# LeftHandPath.net
KiCad netlist of a schematic drawn in EAGLE
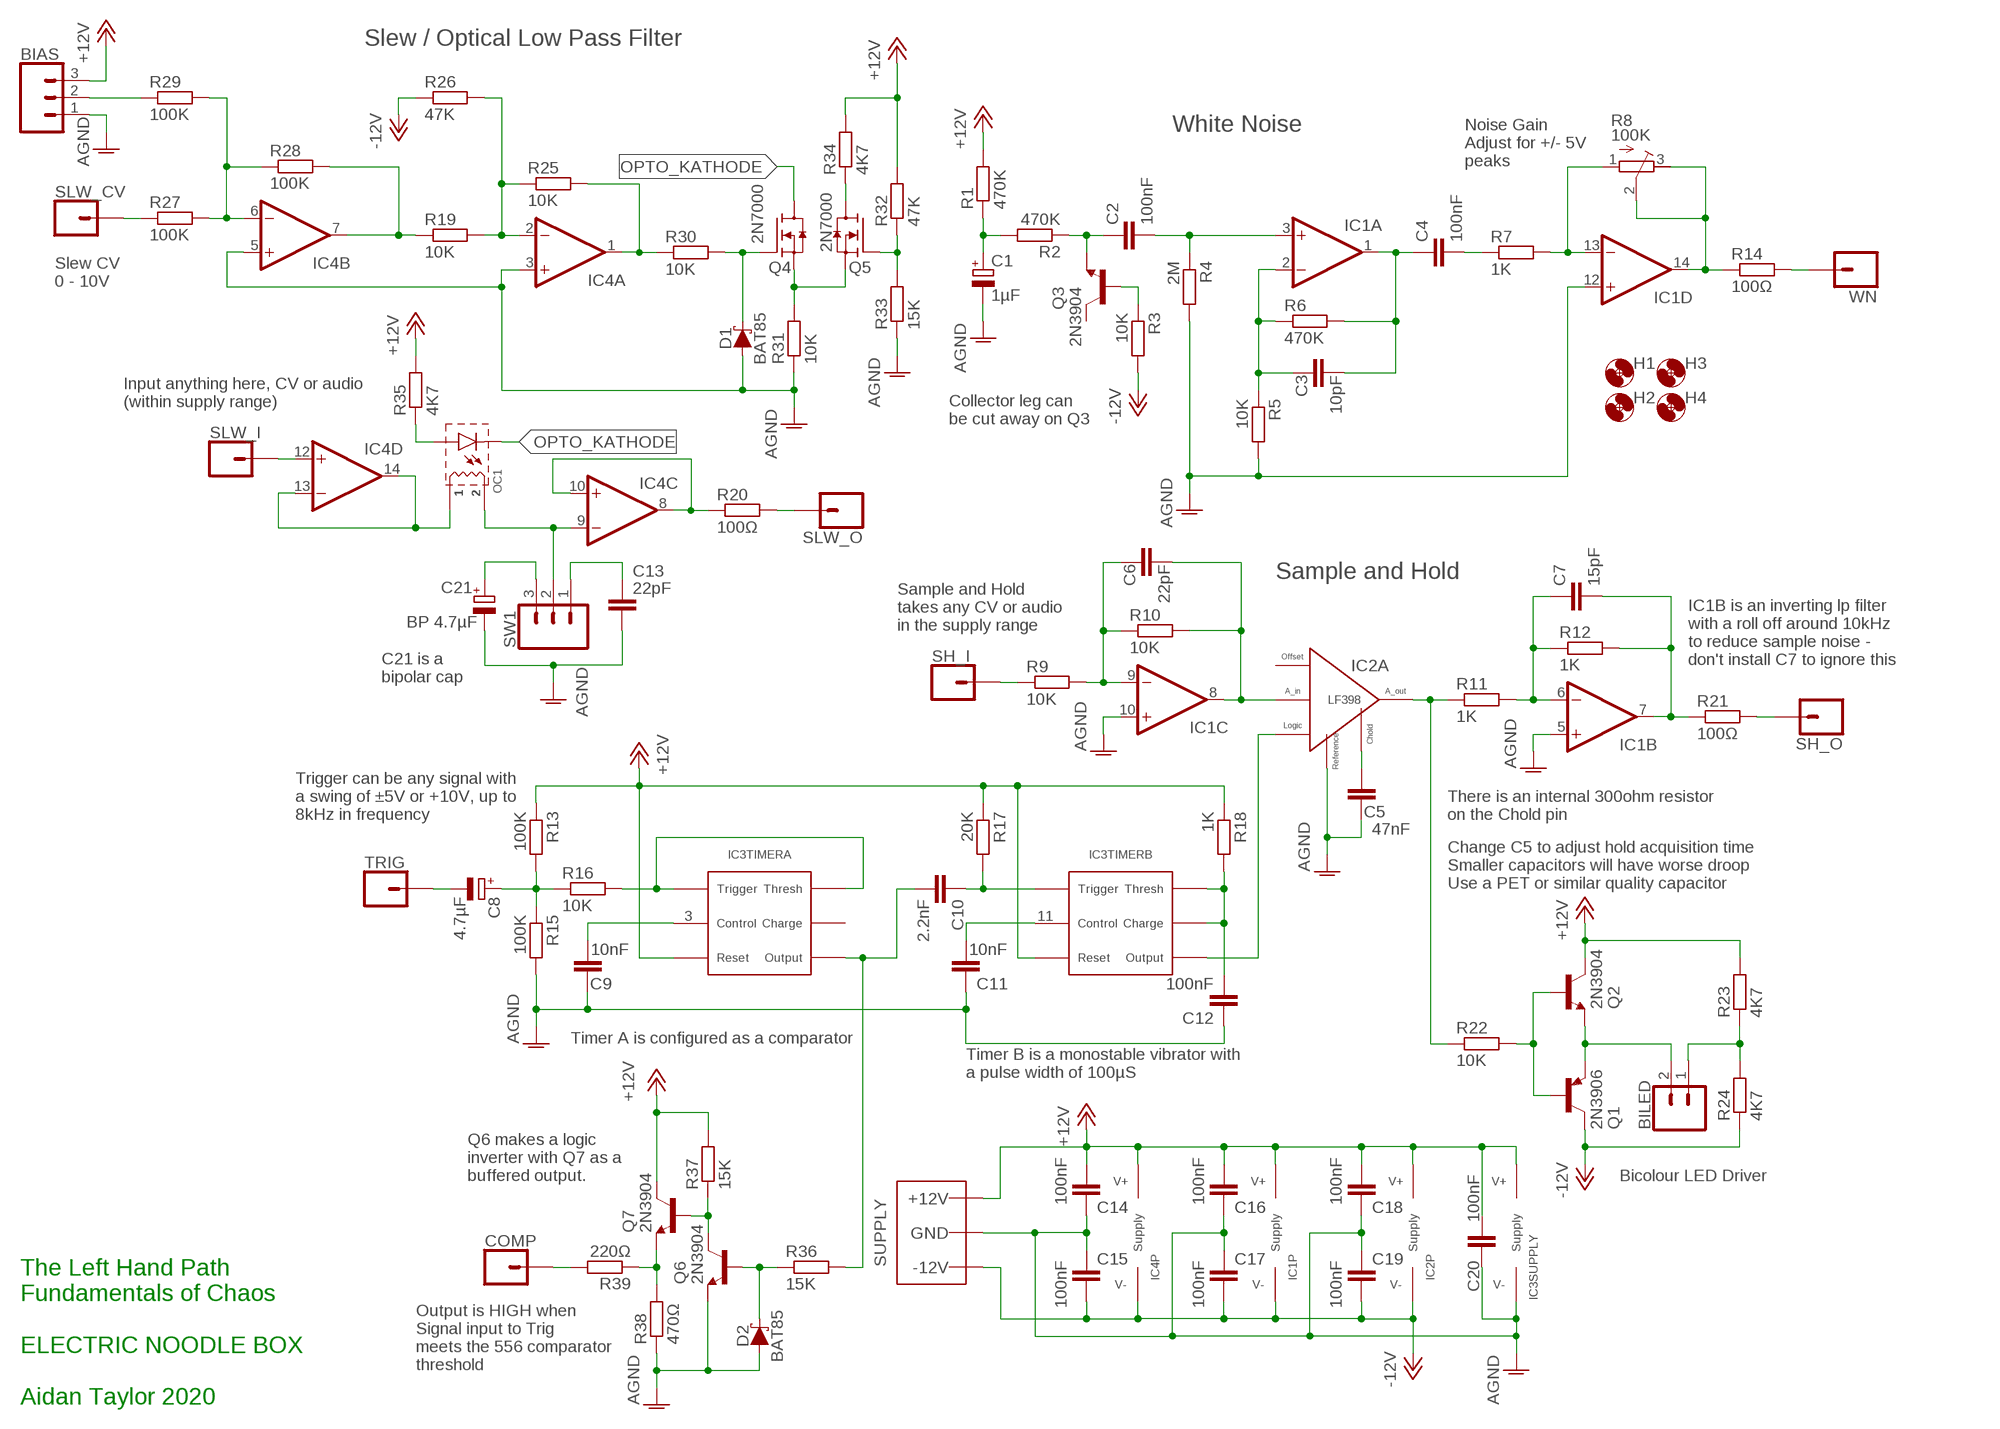
[diagram p0: schematic, sheet 1]

(export (version "E")
  (design (tool "Eeschema 10.0.6"))
  (components
    (comp (ref "BIAS")
      (value "3XWIREPAD")
      (footprint "eagle-import:1X03")
      (libsource (lib "eagle-import") (part "3XWIREPAD"))
    )
    (comp (ref "BILED")
      (value "2XWIREPAD")
      (footprint "eagle-import:1X02")
      (libsource (lib "eagle-import") (part "2XWIREPAD"))
    )
    (comp (ref "C1")
      (value "1µF")
      (footprint "eagle-import:E2-5")
      (libsource (lib "eagle-import") (part "CPOL-EUE2-5"))
    )
    (comp (ref "C2")
      (value "100nF")
      (footprint "eagle-import:C050-025X075")
      (libsource (lib "eagle-import") (part "C-EU050-025X075"))
    )
    (comp (ref "C3")
      (value "10pF")
      (footprint "eagle-import:C050-025X075")
      (libsource (lib "eagle-import") (part "C-EU050-025X075"))
    )
    (comp (ref "C4")
      (value "100nF")
      (footprint "eagle-import:C050-025X075")
      (libsource (lib "eagle-import") (part "C-EU050-025X075"))
    )
    (comp (ref "C5")
      (value "47nF")
      (footprint "eagle-import:C050-025X075")
      (libsource (lib "eagle-import") (part "C-EU050-025X075"))
    )
    (comp (ref "C6")
      (value "22pF")
      (footprint "eagle-import:C050-025X075")
      (libsource (lib "eagle-import") (part "C-EU050-025X075"))
    )
    (comp (ref "C7")
      (value "15pF")
      (footprint "eagle-import:C050-025X075")
      (libsource (lib "eagle-import") (part "C-EU050-025X075"))
    )
    (comp (ref "C8")
      (value "4.7µF")
      (footprint "eagle-import:E2-5")
      (libsource (lib "eagle-import") (part "CPOL-EUE2-5"))
    )
    (comp (ref "C9")
      (value "10nF")
      (footprint "eagle-import:C050-025X075")
      (libsource (lib "eagle-import") (part "C-EU050-025X075"))
    )
    (comp (ref "C10")
      (value "2.2nF")
      (footprint "eagle-import:C050-025X075")
      (libsource (lib "eagle-import") (part "C-EU050-025X075"))
    )
    (comp (ref "C11")
      (value "10nF")
      (footprint "eagle-import:C050-025X075")
      (libsource (lib "eagle-import") (part "C-EU050-025X075"))
    )
    (comp (ref "C12")
      (value "100nF")
      (footprint "eagle-import:C050-025X075")
      (libsource (lib "eagle-import") (part "C-EU050-025X075"))
    )
    (comp (ref "C13")
      (value "22pF")
      (footprint "eagle-import:C050-025X075")
      (libsource (lib "eagle-import") (part "C-EU050-025X075"))
    )
    (comp (ref "C14")
      (value "100nF")
      (footprint "eagle-import:C050-025X075")
      (libsource (lib "eagle-import") (part "C-EU050-025X075"))
    )
    (comp (ref "C15")
      (value "100nF")
      (footprint "eagle-import:C050-025X075")
      (libsource (lib "eagle-import") (part "C-EU050-025X075"))
    )
    (comp (ref "C16")
      (value "100nF")
      (footprint "eagle-import:C050-025X075")
      (libsource (lib "eagle-import") (part "C-EU050-025X075"))
    )
    (comp (ref "C17")
      (value "100nF")
      (footprint "eagle-import:C050-025X075")
      (libsource (lib "eagle-import") (part "C-EU050-025X075"))
    )
    (comp (ref "C18")
      (value "100nF")
      (footprint "eagle-import:C050-025X075")
      (libsource (lib "eagle-import") (part "C-EU050-025X075"))
    )
    (comp (ref "C19")
      (value "100nF")
      (footprint "eagle-import:C050-025X075")
      (libsource (lib "eagle-import") (part "C-EU050-025X075"))
    )
    (comp (ref "C20")
      (value "100nF")
      (footprint "eagle-import:C050-025X075")
      (libsource (lib "eagle-import") (part "C-EU050-025X075"))
    )
    (comp (ref "C21")
      (value "BP 4.7µF")
      (footprint "eagle-import:E2-5")
      (libsource (lib "eagle-import") (part "CPOL-EUE2-5"))
    )
    (comp (ref "COMP")
      (value "1XWIREPAD")
      (footprint "eagle-import:1X01")
      (libsource (lib "eagle-import") (part "1XWIREPAD"))
    )
    (comp (ref "D1")
      (value "BAT85")
      (footprint "eagle-import:DO35-7")
      (libsource (lib "eagle-import") (part "SCHOTTKY_DO35"))
    )
    (comp (ref "D2")
      (value "BAT85")
      (footprint "eagle-import:DO35-7")
      (libsource (lib "eagle-import") (part "SCHOTTKY_DO35"))
    )
    (comp (ref "H1")
      (value "MOUNT-HOLE3.2")
      (footprint "eagle-import:3,2")
      (libsource (lib "eagle-import") (part "MOUNT-HOLE3.2"))
    )
    (comp (ref "H2")
      (value "MOUNT-HOLE3.2")
      (footprint "eagle-import:3,2")
      (libsource (lib "eagle-import") (part "MOUNT-HOLE3.2"))
    )
    (comp (ref "H3")
      (value "MOUNT-HOLE3.2")
      (footprint "eagle-import:3,2")
      (libsource (lib "eagle-import") (part "MOUNT-HOLE3.2"))
    )
    (comp (ref "H4")
      (value "MOUNT-HOLE3.2")
      (footprint "eagle-import:3,2")
      (libsource (lib "eagle-import") (part "MOUNT-HOLE3.2"))
    )
    (comp (ref "IC1")
      (value "TL0X4DIL")
      (footprint "eagle-import:DIL14")
      (libsource (lib "eagle-import") (part "TL0X4DIL"))
    )
    (comp (ref "IC2")
      (value "LF398")
      (footprint "eagle-import:DIL08")
      (libsource (lib "eagle-import") (part "LF398"))
    )
    (comp (ref "IC3")
      (value "556_DUALTIMERDIL14")
      (footprint "eagle-import:DIL14")
      (libsource (lib "eagle-import") (part "556_DUALTIMERDIL14"))
    )
    (comp (ref "IC4")
      (value "TL0X4DIL")
      (footprint "eagle-import:DIL14")
      (libsource (lib "eagle-import") (part "TL0X4DIL"))
    )
    (comp (ref "OC1")
      (value "OPTOCOUPLERSILONEX")
      (footprint "eagle-import:SILONEX_OPTOCOUPLER")
      (libsource (lib "eagle-import") (part "OPTOCOUPLERSILONEX"))
    )
    (comp (ref "Q1")
      (value "2N3906")
      (footprint "eagle-import:TO92")
      (libsource (lib "eagle-import") (part "2N3906"))
    )
    (comp (ref "Q2")
      (value "2N3904")
      (footprint "eagle-import:TO92")
      (libsource (lib "eagle-import") (part "2N3904"))
    )
    (comp (ref "Q3")
      (value "2N3904")
      (footprint "eagle-import:TO92")
      (libsource (lib "eagle-import") (part "2N3904"))
    )
    (comp (ref "Q4")
      (value "2N7000")
      (footprint "eagle-import:TO92")
      (libsource (lib "eagle-import") (part "2N7000"))
    )
    (comp (ref "Q5")
      (value "2N7000")
      (footprint "eagle-import:TO92")
      (libsource (lib "eagle-import") (part "2N7000"))
    )
    (comp (ref "Q6")
      (value "2N3904")
      (footprint "eagle-import:TO92")
      (libsource (lib "eagle-import") (part "2N3904"))
    )
    (comp (ref "Q7")
      (value "2N3904")
      (footprint "eagle-import:TO92")
      (libsource (lib "eagle-import") (part "2N3904"))
    )
    (comp (ref "R1")
      (value "470K")
      (footprint "eagle-import:0207_7")
      (libsource (lib "eagle-import") (part "R-EU_0207/7"))
    )
    (comp (ref "R2")
      (value "470K")
      (footprint "eagle-import:0207_7")
      (libsource (lib "eagle-import") (part "R-EU_0207/7"))
    )
    (comp (ref "R3")
      (value "10K")
      (footprint "eagle-import:0207_7")
      (libsource (lib "eagle-import") (part "R-EU_0207/7"))
    )
    (comp (ref "R4")
      (value "2M")
      (footprint "eagle-import:0207_7")
      (libsource (lib "eagle-import") (part "R-EU_0207/7"))
    )
    (comp (ref "R5")
      (value "10K")
      (footprint "eagle-import:0207_7")
      (libsource (lib "eagle-import") (part "R-EU_0207/7"))
    )
    (comp (ref "R6")
      (value "470K")
      (footprint "eagle-import:0207_7")
      (libsource (lib "eagle-import") (part "R-EU_0207/7"))
    )
    (comp (ref "R7")
      (value "1K")
      (footprint "eagle-import:0207_7")
      (libsource (lib "eagle-import") (part "R-EU_0207/7"))
    )
    (comp (ref "R8")
      (value "100K")
      (footprint "eagle-import:RTRIM3296W")
      (libsource (lib "eagle-import") (part "R-TRIMM3296W"))
    )
    (comp (ref "R9")
      (value "10K")
      (footprint "eagle-import:0207_7")
      (libsource (lib "eagle-import") (part "R-EU_0207/7"))
    )
    (comp (ref "R10")
      (value "10K")
      (footprint "eagle-import:0207_7")
      (libsource (lib "eagle-import") (part "R-EU_0207/7"))
    )
    (comp (ref "R11")
      (value "1K")
      (footprint "eagle-import:0207_7")
      (libsource (lib "eagle-import") (part "R-EU_0207/7"))
    )
    (comp (ref "R12")
      (value "1K")
      (footprint "eagle-import:0207_7")
      (libsource (lib "eagle-import") (part "R-EU_0207/7"))
    )
    (comp (ref "R13")
      (value "100K")
      (footprint "eagle-import:0207_7")
      (libsource (lib "eagle-import") (part "R-EU_0207/7"))
    )
    (comp (ref "R14")
      (value "100Ω")
      (footprint "eagle-import:0207_7")
      (libsource (lib "eagle-import") (part "R-EU_0207/7"))
    )
    (comp (ref "R15")
      (value "100K")
      (footprint "eagle-import:0207_7")
      (libsource (lib "eagle-import") (part "R-EU_0207/7"))
    )
    (comp (ref "R16")
      (value "10K")
      (footprint "eagle-import:0207_7")
      (libsource (lib "eagle-import") (part "R-EU_0207/7"))
    )
    (comp (ref "R17")
      (value "20K")
      (footprint "eagle-import:0207_7")
      (libsource (lib "eagle-import") (part "R-EU_0207/7"))
    )
    (comp (ref "R18")
      (value "1K")
      (footprint "eagle-import:0207_7")
      (libsource (lib "eagle-import") (part "R-EU_0207/7"))
    )
    (comp (ref "R19")
      (value "10K")
      (footprint "eagle-import:0207_7")
      (libsource (lib "eagle-import") (part "R-EU_0207/7"))
    )
    (comp (ref "R20")
      (value "100Ω")
      (footprint "eagle-import:0207_7")
      (libsource (lib "eagle-import") (part "R-EU_0207/7"))
    )
    (comp (ref "R21")
      (value "100Ω")
      (footprint "eagle-import:0207_7")
      (libsource (lib "eagle-import") (part "R-EU_0207/7"))
    )
    (comp (ref "R22")
      (value "10K")
      (footprint "eagle-import:0207_7")
      (libsource (lib "eagle-import") (part "R-EU_0207/7"))
    )
    (comp (ref "R23")
      (value "4K7")
      (footprint "eagle-import:0207_7")
      (libsource (lib "eagle-import") (part "R-EU_0207/7"))
    )
    (comp (ref "R24")
      (value "4K7")
      (footprint "eagle-import:0207_7")
      (libsource (lib "eagle-import") (part "R-EU_0207/7"))
    )
    (comp (ref "R25")
      (value "10K")
      (footprint "eagle-import:0207_7")
      (libsource (lib "eagle-import") (part "R-EU_0207/7"))
    )
    (comp (ref "R26")
      (value "47K")
      (footprint "eagle-import:0207_7")
      (libsource (lib "eagle-import") (part "R-EU_0207/7"))
    )
    (comp (ref "R27")
      (value "100K")
      (footprint "eagle-import:0207_7")
      (libsource (lib "eagle-import") (part "R-EU_0207/7"))
    )
    (comp (ref "R28")
      (value "100K")
      (footprint "eagle-import:0207_7")
      (libsource (lib "eagle-import") (part "R-EU_0207/7"))
    )
    (comp (ref "R29")
      (value "100K")
      (footprint "eagle-import:0207_7")
      (libsource (lib "eagle-import") (part "R-EU_0207/7"))
    )
    (comp (ref "R30")
      (value "10K")
      (footprint "eagle-import:0207_7")
      (libsource (lib "eagle-import") (part "R-EU_0207/7"))
    )
    (comp (ref "R31")
      (value "10K")
      (footprint "eagle-import:0207_7")
      (libsource (lib "eagle-import") (part "R-EU_0207/7"))
    )
    (comp (ref "R32")
      (value "47K")
      (footprint "eagle-import:0207_7")
      (libsource (lib "eagle-import") (part "R-EU_0207/7"))
    )
    (comp (ref "R33")
      (value "15K")
      (footprint "eagle-import:0207_7")
      (libsource (lib "eagle-import") (part "R-EU_0207/7"))
    )
    (comp (ref "R34")
      (value "4K7")
      (footprint "eagle-import:0207_7")
      (libsource (lib "eagle-import") (part "R-EU_0207/7"))
    )
    (comp (ref "R35")
      (value "4K7")
      (footprint "eagle-import:0207_7")
      (libsource (lib "eagle-import") (part "R-EU_0207/7"))
    )
    (comp (ref "R36")
      (value "15K")
      (footprint "eagle-import:0207_7")
      (libsource (lib "eagle-import") (part "R-EU_0207/7"))
    )
    (comp (ref "R37")
      (value "15K")
      (footprint "eagle-import:0207_7")
      (libsource (lib "eagle-import") (part "R-EU_0207/7"))
    )
    (comp (ref "R38")
      (value "470Ω")
      (footprint "eagle-import:0207_7")
      (libsource (lib "eagle-import") (part "R-EU_0207/7"))
    )
    (comp (ref "R39")
      (value "220Ω")
      (footprint "eagle-import:0207_7")
      (libsource (lib "eagle-import") (part "R-EU_0207/7"))
    )
    (comp (ref "SH_I")
      (value "1XWIREPAD")
      (footprint "eagle-import:1X01")
      (libsource (lib "eagle-import") (part "1XWIREPAD"))
    )
    (comp (ref "SH_O")
      (value "1XWIREPAD")
      (footprint "eagle-import:1X01")
      (libsource (lib "eagle-import") (part "1XWIREPAD"))
    )
    (comp (ref "SLW_CV")
      (value "1XWIREPAD")
      (footprint "eagle-import:1X01")
      (libsource (lib "eagle-import") (part "1XWIREPAD"))
    )
    (comp (ref "SLW_I")
      (value "1XWIREPAD")
      (footprint "eagle-import:1X01")
      (libsource (lib "eagle-import") (part "1XWIREPAD"))
    )
    (comp (ref "SLW_O")
      (value "1XWIREPAD")
      (footprint "eagle-import:1X01")
      (libsource (lib "eagle-import") (part "1XWIREPAD"))
    )
    (comp (ref "SW1")
      (value "3XWIREPAD")
      (footprint "eagle-import:1X03")
      (libsource (lib "eagle-import") (part "3XWIREPAD"))
    )
    (comp (ref "TRIG")
      (value "1XWIREPAD")
      (footprint "eagle-import:1X01")
      (libsource (lib "eagle-import") (part "1XWIREPAD"))
    )
    (comp (ref "WN")
      (value "1XWIREPAD")
      (footprint "eagle-import:1X01")
      (libsource (lib "eagle-import") (part "1XWIREPAD"))
    )
    (comp (ref "WP1")
      (value "COMBO_SUPPLY_HEADER")
      (footprint "eagle-import:COMBINED_POWER")
      (libsource (lib "eagle-import") (part "COMBO_SUPPLY_HEADER"))
    )
  )
  (nets
    (net (code "1") (name "+12V") (class "Default")
      (node (ref "BIAS") (pin "3") (pinfunction "3_3") (pintype "passive"))
      (node (ref "C14") (pin "2") (pinfunction "2_2") (pintype "passive"))
      (node (ref "C16") (pin "2") (pinfunction "2_2") (pintype "passive"))
      (node (ref "C18") (pin "2") (pinfunction "2_2") (pintype "passive"))
      (node (ref "C20") (pin "2") (pinfunction "2_2") (pintype "passive"))
      (node (ref "IC1") (pin "4") (pinfunction "V+_4") (pintype "bidirectional"))
      (node (ref "IC2") (pin "1") (pinfunction "V+_1") (pintype "bidirectional"))
      (node (ref "IC3") (pin "10") (pinfunction "RESET_10") (pintype "bidirectional"))
      (node (ref "IC3") (pin "14") (pinfunction "V+_14") (pintype "bidirectional"))
      (node (ref "IC3") (pin "4") (pinfunction "RESET_4") (pintype "bidirectional"))
      (node (ref "IC4") (pin "4") (pinfunction "V+_4") (pintype "bidirectional"))
      (node (ref "Q2") (pin "1") (pinfunction "C_1") (pintype "passive"))
      (node (ref "Q7") (pin "1") (pinfunction "C_1") (pintype "passive"))
      (node (ref "R1") (pin "2") (pinfunction "2_2") (pintype "passive"))
      (node (ref "R13") (pin "1") (pinfunction "1_1") (pintype "passive"))
      (node (ref "R17") (pin "1") (pinfunction "1_1") (pintype "passive"))
      (node (ref "R18") (pin "1") (pinfunction "1_1") (pintype "passive"))
      (node (ref "R23") (pin "2") (pinfunction "2_2") (pintype "passive"))
      (node (ref "R32") (pin "2") (pinfunction "2_2") (pintype "passive"))
      (node (ref "R34") (pin "2") (pinfunction "2_2") (pintype "passive"))
      (node (ref "R35") (pin "2") (pinfunction "2_2") (pintype "passive"))
      (node (ref "R37") (pin "2") (pinfunction "2_2") (pintype "passive"))
      (node (ref "WP1") (pin "V+1") (pinfunction "V++_V+1") (pintype "power_in"))
      (node (ref "WP1") (pin "V+2") (pinfunction "V++_V+2") (pintype "power_in"))
      (node (ref "WP1") (pin "V+3") (pinfunction "V++_V+3") (pintype "power_in"))
    )
    (net (code "2") (name "-12V") (class "Default")
      (node (ref "C15") (pin "1") (pinfunction "1_1") (pintype "passive"))
      (node (ref "C17") (pin "1") (pinfunction "1_1") (pintype "passive"))
      (node (ref "C19") (pin "1") (pinfunction "1_1") (pintype "passive"))
      (node (ref "IC1") (pin "11") (pinfunction "V-_11") (pintype "bidirectional"))
      (node (ref "IC2") (pin "4") (pinfunction "V-_4") (pintype "bidirectional"))
      (node (ref "IC4") (pin "11") (pinfunction "V-_11") (pintype "bidirectional"))
      (node (ref "Q1") (pin "1") (pinfunction "C_1") (pintype "passive"))
      (node (ref "R24") (pin "1") (pinfunction "1_1") (pintype "passive"))
      (node (ref "R26") (pin "1") (pinfunction "1_1") (pintype "passive"))
      (node (ref "R3") (pin "2") (pinfunction "2_2") (pintype "passive"))
      (node (ref "WP1") (pin "V-1") (pinfunction "V--_V-1") (pintype "power_in"))
      (node (ref "WP1") (pin "V-2") (pinfunction "V--_V-2") (pintype "power_in"))
      (node (ref "WP1") (pin "V-3") (pinfunction "V--_V-3") (pintype "power_in"))
    )
    (net (code "3") (name "AGND") (class "Default")
      (node (ref "BIAS") (pin "1") (pinfunction "1_1") (pintype "passive"))
      (node (ref "C1") (pin "-") (pinfunction "-_-") (pintype "passive"))
      (node (ref "C11") (pin "1") (pinfunction "1_1") (pintype "passive"))
      (node (ref "C12") (pin "1") (pinfunction "1_1") (pintype "passive"))
      (node (ref "C13") (pin "1") (pinfunction "1_1") (pintype "passive"))
      (node (ref "C14") (pin "1") (pinfunction "1_1") (pintype "passive"))
      (node (ref "C15") (pin "2") (pinfunction "2_2") (pintype "passive"))
      (node (ref "C16") (pin "1") (pinfunction "1_1") (pintype "passive"))
      (node (ref "C17") (pin "2") (pinfunction "2_2") (pintype "passive"))
      (node (ref "C18") (pin "1") (pinfunction "1_1") (pintype "passive"))
      (node (ref "C19") (pin "2") (pinfunction "2_2") (pintype "passive"))
      (node (ref "C20") (pin "1") (pinfunction "1_1") (pintype "passive"))
      (node (ref "C21") (pin "-") (pinfunction "-_-") (pintype "passive"))
      (node (ref "C5") (pin "1") (pinfunction "1_1") (pintype "passive"))
      (node (ref "C9") (pin "1") (pinfunction "1_1") (pintype "passive"))
      (node (ref "D1") (pin "A") (pinfunction "A_A") (pintype "passive"))
      (node (ref "D2") (pin "A") (pinfunction "A_A") (pintype "passive"))
      (node (ref "IC1") (pin "10") (pinfunction "+IN_10") (pintype "input"))
      (node (ref "IC1") (pin "12") (pinfunction "+IN_12") (pintype "input"))
      (node (ref "IC1") (pin "5") (pinfunction "+IN_5") (pintype "input"))
      (node (ref "IC2") (pin "7") (pinfunction "REFERENCE_7") (pintype "input"))
      (node (ref "IC3") (pin "7") (pinfunction "V-_7") (pintype "bidirectional"))
      (node (ref "IC4") (pin "3") (pinfunction "+IN_3") (pintype "input"))
      (node (ref "IC4") (pin "5") (pinfunction "+IN_5") (pintype "input"))
      (node (ref "Q6") (pin "3") (pinfunction "E_3") (pintype "passive"))
      (node (ref "R15") (pin "2") (pinfunction "2_2") (pintype "passive"))
      (node (ref "R31") (pin "1") (pinfunction "1_1") (pintype "passive"))
      (node (ref "R33") (pin "1") (pinfunction "1_1") (pintype "passive"))
      (node (ref "R38") (pin "1") (pinfunction "1_1") (pintype "passive"))
      (node (ref "R4") (pin "2") (pinfunction "2_2") (pintype "passive"))
      (node (ref "R5") (pin "2") (pinfunction "2_2") (pintype "passive"))
      (node (ref "WP1") (pin "GND1") (pinfunction "AGND_GND1") (pintype "power_in"))
      (node (ref "WP1") (pin "GND2") (pinfunction "AGND_GND2") (pintype "power_in"))
      (node (ref "WP1") (pin "GND3") (pinfunction "AGND_GND3") (pintype "power_in"))
      (node (ref "WP1") (pin "GND4") (pinfunction "AGND_GND4") (pintype "power_in"))
      (node (ref "WP1") (pin "GND5") (pinfunction "AGND_GND5") (pintype "power_in"))
      (node (ref "WP1") (pin "GND6") (pinfunction "AGND_GND6") (pintype "power_in"))
      (node (ref "WP1") (pin "GND7") (pinfunction "AGND_GND7") (pintype "power_in"))
      (node (ref "WP1") (pin "GND8") (pinfunction "AGND_GND8") (pintype "power_in"))
    )
    (net (code "4") (name "Net-(BIAS-Pad2)") (class "Default")
      (node (ref "BIAS") (pin "2") (pinfunction "2_2") (pintype "passive"))
      (node (ref "R29") (pin "1") (pinfunction "1_1") (pintype "passive"))
    )
    (net (code "5") (name "Net-(BILED-Pad1)") (class "Default")
      (node (ref "BILED") (pin "1") (pinfunction "1_1") (pintype "passive"))
      (node (ref "R23") (pin "1") (pinfunction "1_1") (pintype "passive"))
      (node (ref "R24") (pin "2") (pinfunction "2_2") (pintype "passive"))
    )
    (net (code "6") (name "Net-(C1-Pad+)") (class "Default")
      (node (ref "C1") (pin "+") (pinfunction "+_+") (pintype "passive"))
      (node (ref "R1") (pin "1") (pinfunction "1_1") (pintype "passive"))
      (node (ref "R2") (pin "2") (pinfunction "2_2") (pintype "passive"))
    )
    (net (code "7") (name "Net-(C4-Pad2)") (class "Default")
      (node (ref "C4") (pin "2") (pinfunction "2_2") (pintype "passive"))
      (node (ref "R7") (pin "1") (pinfunction "1_1") (pintype "passive"))
    )
    (net (code "8") (name "Net-(C8-Pad+)") (class "Default")
      (node (ref "C8") (pin "+") (pinfunction "+_+") (pintype "passive"))
      (node (ref "R13") (pin "2") (pinfunction "2_2") (pintype "passive"))
      (node (ref "R15") (pin "1") (pinfunction "1_1") (pintype "passive"))
      (node (ref "R16") (pin "1") (pinfunction "1_1") (pintype "passive"))
    )
    (net (code "9") (name "Net-(C8-Pad-)") (class "Default")
      (node (ref "C8") (pin "-") (pinfunction "-_-") (pintype "passive"))
      (node (ref "TRIG") (pin "1") (pinfunction "1_1") (pintype "passive"))
    )
    (net (code "10") (name "Net-(C13-Pad2)") (class "Default")
      (node (ref "C13") (pin "2") (pinfunction "2_2") (pintype "passive"))
      (node (ref "SW1") (pin "1") (pinfunction "1_1") (pintype "passive"))
    )
    (net (code "11") (name "Net-(C21-Pad+)") (class "Default")
      (node (ref "C21") (pin "+") (pinfunction "+_+") (pintype "passive"))
      (node (ref "SW1") (pin "3") (pinfunction "3_3") (pintype "passive"))
    )
    (net (code "12") (name "Net-(COMP-Pad1)") (class "Default")
      (node (ref "COMP") (pin "1") (pinfunction "1_1") (pintype "passive"))
      (node (ref "R39") (pin "2") (pinfunction "2_2") (pintype "passive"))
    )
    (net (code "13") (name "Net-(IC1A-+IN)") (class "Default")
      (node (ref "C2") (pin "2") (pinfunction "2_2") (pintype "passive"))
      (node (ref "IC1") (pin "3") (pinfunction "+IN_3") (pintype "input"))
      (node (ref "R4") (pin "1") (pinfunction "1_1") (pintype "passive"))
    )
    (net (code "14") (name "Net-(IC1A--IN)") (class "Default")
      (node (ref "C3") (pin "1") (pinfunction "1_1") (pintype "passive"))
      (node (ref "IC1") (pin "2") (pinfunction "-IN_2") (pintype "input"))
      (node (ref "R5") (pin "1") (pinfunction "1_1") (pintype "passive"))
      (node (ref "R6") (pin "1") (pinfunction "1_1") (pintype "passive"))
    )
    (net (code "15") (name "Net-(IC1A-OUT)") (class "Default")
      (node (ref "C3") (pin "2") (pinfunction "2_2") (pintype "passive"))
      (node (ref "C4") (pin "1") (pinfunction "1_1") (pintype "passive"))
      (node (ref "IC1") (pin "1") (pinfunction "OUT_1") (pintype "output"))
      (node (ref "R6") (pin "2") (pinfunction "2_2") (pintype "passive"))
    )
    (net (code "16") (name "Net-(IC1B--IN)") (class "Default")
      (node (ref "C7") (pin "1") (pinfunction "1_1") (pintype "passive"))
      (node (ref "IC1") (pin "6") (pinfunction "-IN_6") (pintype "input"))
      (node (ref "R11") (pin "2") (pinfunction "2_2") (pintype "passive"))
      (node (ref "R12") (pin "1") (pinfunction "1_1") (pintype "passive"))
    )
    (net (code "17") (name "Net-(IC1B-OUT)") (class "Default")
      (node (ref "C7") (pin "2") (pinfunction "2_2") (pintype "passive"))
      (node (ref "IC1") (pin "7") (pinfunction "OUT_7") (pintype "output"))
      (node (ref "R12") (pin "2") (pinfunction "2_2") (pintype "passive"))
      (node (ref "R21") (pin "1") (pinfunction "1_1") (pintype "passive"))
    )
    (net (code "18") (name "Net-(IC1C--IN)") (class "Default")
      (node (ref "C6") (pin "1") (pinfunction "1_1") (pintype "passive"))
      (node (ref "IC1") (pin "9") (pinfunction "-IN_9") (pintype "input"))
      (node (ref "R10") (pin "1") (pinfunction "1_1") (pintype "passive"))
      (node (ref "R9") (pin "2") (pinfunction "2_2") (pintype "passive"))
    )
    (net (code "19") (name "Net-(IC1C-OUT)") (class "Default")
      (node (ref "C6") (pin "2") (pinfunction "2_2") (pintype "passive"))
      (node (ref "IC1") (pin "8") (pinfunction "OUT_8") (pintype "output"))
      (node (ref "IC2") (pin "3") (pinfunction "ANALOG_IN_3") (pintype "input"))
      (node (ref "R10") (pin "2") (pinfunction "2_2") (pintype "passive"))
    )
    (net (code "20") (name "Net-(IC1D--IN)") (class "Default")
      (node (ref "IC1") (pin "13") (pinfunction "-IN_13") (pintype "input"))
      (node (ref "R7") (pin "2") (pinfunction "2_2") (pintype "passive"))
      (node (ref "R8") (pin "1") (pinfunction "A_1") (pintype "passive"))
    )
    (net (code "21") (name "Net-(IC1D-OUT)") (class "Default")
      (node (ref "IC1") (pin "14") (pinfunction "OUT_14") (pintype "output"))
      (node (ref "R14") (pin "1") (pinfunction "1_1") (pintype "passive"))
      (node (ref "R8") (pin "2") (pinfunction "S_2") (pintype "passive"))
      (node (ref "R8") (pin "3") (pinfunction "E_3") (pintype "passive"))
    )
    (net (code "22") (name "Net-(IC2A-ANALOG_OUT)") (class "Default")
      (node (ref "IC2") (pin "5") (pinfunction "ANALOG_OUT_5") (pintype "output"))
      (node (ref "R11") (pin "1") (pinfunction "1_1") (pintype "passive"))
      (node (ref "R22") (pin "1") (pinfunction "1_1") (pintype "passive"))
    )
    (net (code "23") (name "Net-(IC2A-CH)") (class "Default")
      (node (ref "C5") (pin "2") (pinfunction "2_2") (pintype "passive"))
      (node (ref "IC2") (pin "6") (pinfunction "CH_6") (pintype "input"))
    )
    (net (code "24") (name "Net-(IC2A-LOGIC)") (class "Default")
      (node (ref "IC2") (pin "8") (pinfunction "LOGIC_8") (pintype "input"))
      (node (ref "IC3") (pin "9") (pinfunction "OUTPUT_9") (pintype "bidirectional"))
    )
    (net (code "25") (name "Net-(IC3B-CONT)") (class "Default")
      (node (ref "C9") (pin "2") (pinfunction "2_2") (pintype "passive"))
      (node (ref "IC3") (pin "3") (pinfunction "CONT_3") (pintype "bidirectional"))
    )
    (net (code "26") (name "Net-(IC3B-OUTPUT)") (class "Default")
      (node (ref "C10") (pin "2") (pinfunction "2_2") (pintype "passive"))
      (node (ref "IC3") (pin "5") (pinfunction "OUTPUT_5") (pintype "bidirectional"))
      (node (ref "R36") (pin "2") (pinfunction "2_2") (pintype "passive"))
    )
    (net (code "27") (name "Net-(IC3B-THRESHOLD)") (class "Default")
      (node (ref "IC3") (pin "2") (pinfunction "THRESHOLD_2") (pintype "bidirectional"))
      (node (ref "IC3") (pin "6") (pinfunction "TRIGGER_6") (pintype "bidirectional"))
      (node (ref "R16") (pin "2") (pinfunction "2_2") (pintype "passive"))
    )
    (net (code "28") (name "Net-(IC3C-CONT)") (class "Default")
      (node (ref "C11") (pin "2") (pinfunction "2_2") (pintype "passive"))
      (node (ref "IC3") (pin "11") (pinfunction "CONT_11") (pintype "bidirectional"))
    )
    (net (code "29") (name "Net-(IC3C-DISCHARGE)") (class "Default")
      (node (ref "C12") (pin "2") (pinfunction "2_2") (pintype "passive"))
      (node (ref "IC3") (pin "12") (pinfunction "THRESHOLD_12") (pintype "bidirectional"))
      (node (ref "IC3") (pin "13") (pinfunction "DISCHARGE_13") (pintype "bidirectional"))
      (node (ref "R18") (pin "2") (pinfunction "2_2") (pintype "passive"))
    )
    (net (code "30") (name "Net-(IC3C-TRIGGER)") (class "Default")
      (node (ref "C10") (pin "1") (pinfunction "1_1") (pintype "passive"))
      (node (ref "IC3") (pin "8") (pinfunction "TRIGGER_8") (pintype "bidirectional"))
      (node (ref "R17") (pin "2") (pinfunction "2_2") (pintype "passive"))
    )
    (net (code "31") (name "Net-(IC4A--IN)") (class "Default")
      (node (ref "IC4") (pin "2") (pinfunction "-IN_2") (pintype "input"))
      (node (ref "R19") (pin "2") (pinfunction "2_2") (pintype "passive"))
      (node (ref "R25") (pin "1") (pinfunction "1_1") (pintype "passive"))
      (node (ref "R26") (pin "2") (pinfunction "2_2") (pintype "passive"))
    )
    (net (code "32") (name "Net-(IC4A-OUT)") (class "Default")
      (node (ref "IC4") (pin "1") (pinfunction "OUT_1") (pintype "output"))
      (node (ref "R25") (pin "2") (pinfunction "2_2") (pintype "passive"))
      (node (ref "R30") (pin "1") (pinfunction "1_1") (pintype "passive"))
    )
    (net (code "33") (name "Net-(IC4B--IN)") (class "Default")
      (node (ref "IC4") (pin "6") (pinfunction "-IN_6") (pintype "input"))
      (node (ref "R27") (pin "2") (pinfunction "2_2") (pintype "passive"))
      (node (ref "R28") (pin "1") (pinfunction "1_1") (pintype "passive"))
      (node (ref "R29") (pin "2") (pinfunction "2_2") (pintype "passive"))
    )
    (net (code "34") (name "Net-(IC4B-OUT)") (class "Default")
      (node (ref "IC4") (pin "7") (pinfunction "OUT_7") (pintype "output"))
      (node (ref "R19") (pin "1") (pinfunction "1_1") (pintype "passive"))
      (node (ref "R28") (pin "2") (pinfunction "2_2") (pintype "passive"))
    )
    (net (code "35") (name "Net-(IC4C-+IN)") (class "Default")
      (node (ref "IC4") (pin "10") (pinfunction "+IN_10") (pintype "input"))
      (node (ref "IC4") (pin "8") (pinfunction "OUT_8") (pintype "output"))
      (node (ref "R20") (pin "1") (pinfunction "1_1") (pintype "passive"))
    )
    (net (code "36") (name "Net-(IC4C--IN)") (class "Default")
      (node (ref "IC4") (pin "9") (pinfunction "-IN_9") (pintype "input"))
      (node (ref "OC1") (pin "2") (pinfunction "R2_2") (pintype "bidirectional"))
      (node (ref "SW1") (pin "2") (pinfunction "2_2") (pintype "passive"))
    )
    (net (code "37") (name "Net-(IC4D-+IN)") (class "Default")
      (node (ref "IC4") (pin "12") (pinfunction "+IN_12") (pintype "input"))
      (node (ref "SLW_I") (pin "1") (pinfunction "1_1") (pintype "passive"))
    )
    (net (code "38") (name "Net-(IC4D--IN)") (class "Default")
      (node (ref "IC4") (pin "13") (pinfunction "-IN_13") (pintype "input"))
      (node (ref "IC4") (pin "14") (pinfunction "OUT_14") (pintype "output"))
      (node (ref "OC1") (pin "1") (pinfunction "R1_1") (pintype "bidirectional"))
    )
    (net (code "39") (name "Net-(OC1-PadA)") (class "Default")
      (node (ref "OC1") (pin "A") (pinfunction "A_A") (pintype "passive"))
      (node (ref "R35") (pin "1") (pinfunction "1_1") (pintype "passive"))
    )
    (net (code "40") (name "Net-(Q1-B)") (class "Default")
      (node (ref "Q1") (pin "2") (pinfunction "B_2") (pintype "passive"))
      (node (ref "Q2") (pin "2") (pinfunction "B_2") (pintype "passive"))
      (node (ref "R22") (pin "2") (pinfunction "2_2") (pintype "passive"))
    )
    (net (code "41") (name "Net-(Q1-E)") (class "Default")
      (node (ref "BILED") (pin "2") (pinfunction "2_2") (pintype "passive"))
      (node (ref "Q1") (pin "3") (pinfunction "E_3") (pintype "passive"))
      (node (ref "Q2") (pin "3") (pinfunction "E_3") (pintype "passive"))
    )
    (net (code "42") (name "Net-(Q3-B)") (class "Default")
      (node (ref "Q3") (pin "2") (pinfunction "B_2") (pintype "passive"))
      (node (ref "R3") (pin "1") (pinfunction "1_1") (pintype "passive"))
    )
    (net (code "43") (name "Net-(Q3-E)") (class "Default")
      (node (ref "C2") (pin "1") (pinfunction "1_1") (pintype "passive"))
      (node (ref "Q3") (pin "3") (pinfunction "E_3") (pintype "passive"))
      (node (ref "R2") (pin "1") (pinfunction "1_1") (pintype "passive"))
    )
    (net (code "44") (name "Net-(Q4-G)") (class "Default")
      (node (ref "D1") (pin "C") (pinfunction "C_C") (pintype "passive"))
      (node (ref "Q4") (pin "2") (pinfunction "G_2") (pintype "passive"))
      (node (ref "R30") (pin "2") (pinfunction "2_2") (pintype "passive"))
    )
    (net (code "45") (name "Net-(Q4-S)") (class "Default")
      (node (ref "Q4") (pin "1") (pinfunction "S_1") (pintype "passive"))
      (node (ref "Q5") (pin "1") (pinfunction "S_1") (pintype "passive"))
      (node (ref "R31") (pin "2") (pinfunction "2_2") (pintype "passive"))
    )
    (net (code "46") (name "Net-(Q5-D)") (class "Default")
      (node (ref "Q5") (pin "3") (pinfunction "D_3") (pintype "passive"))
      (node (ref "R34") (pin "1") (pinfunction "1_1") (pintype "passive"))
    )
    (net (code "47") (name "Net-(Q5-G)") (class "Default")
      (node (ref "Q5") (pin "2") (pinfunction "G_2") (pintype "passive"))
      (node (ref "R32") (pin "1") (pinfunction "1_1") (pintype "passive"))
      (node (ref "R33") (pin "2") (pinfunction "2_2") (pintype "passive"))
    )
    (net (code "48") (name "Net-(Q6-B)") (class "Default")
      (node (ref "D2") (pin "C") (pinfunction "C_C") (pintype "passive"))
      (node (ref "Q6") (pin "2") (pinfunction "B_2") (pintype "passive"))
      (node (ref "R36") (pin "1") (pinfunction "1_1") (pintype "passive"))
    )
    (net (code "49") (name "Net-(Q6-C)") (class "Default")
      (node (ref "Q6") (pin "1") (pinfunction "C_1") (pintype "passive"))
      (node (ref "Q7") (pin "2") (pinfunction "B_2") (pintype "passive"))
      (node (ref "R37") (pin "1") (pinfunction "1_1") (pintype "passive"))
    )
    (net (code "50") (name "Net-(Q7-E)") (class "Default")
      (node (ref "Q7") (pin "3") (pinfunction "E_3") (pintype "passive"))
      (node (ref "R38") (pin "2") (pinfunction "2_2") (pintype "passive"))
      (node (ref "R39") (pin "1") (pinfunction "1_1") (pintype "passive"))
    )
    (net (code "51") (name "Net-(R9-Pad1)") (class "Default")
      (node (ref "R9") (pin "1") (pinfunction "1_1") (pintype "passive"))
      (node (ref "SH_I") (pin "1") (pinfunction "1_1") (pintype "passive"))
    )
    (net (code "52") (name "Net-(R14-Pad2)") (class "Default")
      (node (ref "R14") (pin "2") (pinfunction "2_2") (pintype "passive"))
      (node (ref "WN") (pin "1") (pinfunction "1_1") (pintype "passive"))
    )
    (net (code "53") (name "Net-(R20-Pad2)") (class "Default")
      (node (ref "R20") (pin "2") (pinfunction "2_2") (pintype "passive"))
      (node (ref "SLW_O") (pin "1") (pinfunction "1_1") (pintype "passive"))
    )
    (net (code "54") (name "Net-(R21-Pad2)") (class "Default")
      (node (ref "R21") (pin "2") (pinfunction "2_2") (pintype "passive"))
      (node (ref "SH_O") (pin "1") (pinfunction "1_1") (pintype "passive"))
    )
    (net (code "55") (name "Net-(R27-Pad1)") (class "Default")
      (node (ref "R27") (pin "1") (pinfunction "1_1") (pintype "passive"))
      (node (ref "SLW_CV") (pin "1") (pinfunction "1_1") (pintype "passive"))
    )
    (net (code "56") (name "OPTO_KATHODE") (class "Default")
      (node (ref "OC1") (pin "K") (pinfunction "K_K") (pintype "passive"))
      (node (ref "Q4") (pin "3") (pinfunction "D_3") (pintype "passive"))
    )
    (net (code "57") (name "unconnected-(IC2A-OFFSET-Pad2)") (class "Default")
      (node (ref "IC2") (pin "2") (pinfunction "OFFSET_2") (pintype "input"))
    )
    (net (code "58") (name "unconnected-(IC3B-DISCHARGE-Pad1)") (class "Default")
      (node (ref "IC3") (pin "1") (pinfunction "DISCHARGE_1") (pintype "bidirectional"))
    )
    (net (code "59") (name "unconnected-(Q3-C-Pad1)") (class "Default")
      (node (ref "Q3") (pin "1") (pinfunction "C_1") (pintype "passive"))
    )
  )
)
